# SupplyDigital.net
KiCad netlist of a schematic drawn in Altium Designer
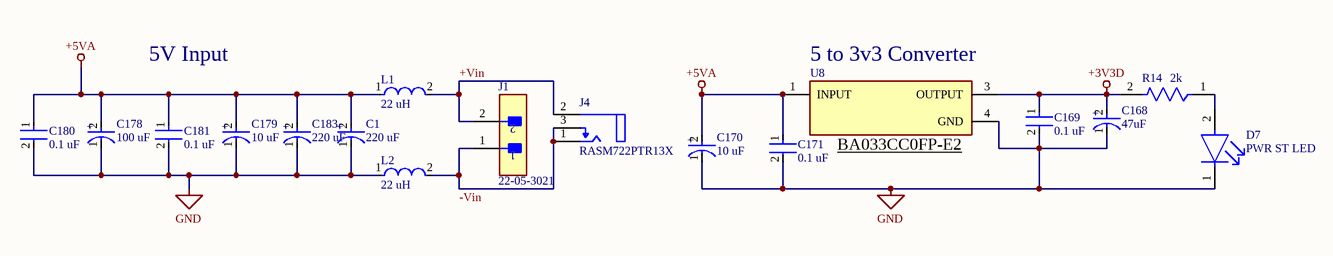
[diagram p0: SupplyDigital.SchDoc]

(export (version "E")
  (design (tool "Eeschema 10.0.6"))
  (components
    (comp (ref "C1")
      (value "220 uF")
      (footprint "FP-SC-MFG")
      (description "CAP ALUM 100UF 20% 10V SMD")
      (fields (field (name "TOLERANCE") "20%"))
      (libsource (lib "Altium Content Vault") (part "a00bbbee19879c290e62620ae7e47b1"))
    )
    (comp (ref "C168")
      (value "47uF")
      (footprint "FP-TAJR-MFG")
      (description "4.7uF 10V  ±10% 9Ω 0805  SMD Tantalum Capacitor")
      (fields (field (name "TOLERANCE") "10%") (field (name "VOLTAGE") "10V"))
      (libsource (lib "Altium Content Vault") (part "203bc49f2ac43e59fd269a8c329ed05"))
    )
    (comp (ref "C169")
      (value "0.1 uF")
      (footprint "FP-CC0805-0_85-MFG")
      (description "CAP CER 0.1UF 25V X7R 0805")
      (fields (field (name "MANUFACTURER PART NUMBER") "CC0805KRX7R8BB104") (field (name "TOLERANCE") "0.1"))
      (libsource (lib "Altium Content Vault") (part "11868f565c42a9108669ba33697ecf6"))
    )
    (comp (ref "C170")
      (value "10 uF")
      (footprint "FP-TAJR-MFG")
      (description "4.7uF 10V  ±10% 9Ω 0805  SMD Tantalum Capacitor")
      (fields (field (name "TOLERANCE") "10%") (field (name "VOLTAGE") "10V"))
      (libsource (lib "Altium Content Vault") (part "203bc49f2ac43e59fd269a8c329ed05"))
    )
    (comp (ref "C171")
      (value "0.1 uF")
      (footprint "FP-CC0805-0_85-MFG")
      (description "CAP CER 0.1UF 25V X7R 0805")
      (fields (field (name "MANUFACTURER PART NUMBER") "CC0805KRX7R8BB104") (field (name "TOLERANCE") "0.1"))
      (libsource (lib "Altium Content Vault") (part "11868f565c42a9108669ba33697ecf6"))
    )
    (comp (ref "C178")
      (value "100 uF")
      (footprint "FP-TAJR-MFG")
      (description "4.7uF 10V  ±10% 9Ω 0805  SMD Tantalum Capacitor")
      (fields (field (name "TOLERANCE") "10%") (field (name "VOLTAGE") "10V"))
      (libsource (lib "Altium Content Vault") (part "203bc49f2ac43e59fd269a8c329ed05"))
    )
    (comp (ref "C179")
      (value "10 uF")
      (footprint "FP-TAJR-MFG")
      (description "4.7uF 10V  ±10% 9Ω 0805  SMD Tantalum Capacitor")
      (fields (field (name "TOLERANCE") "10%") (field (name "VOLTAGE") "10V"))
      (libsource (lib "Altium Content Vault") (part "203bc49f2ac43e59fd269a8c329ed05"))
    )
    (comp (ref "C180")
      (value "0.1 uF")
      (footprint "FP-CC0805-0_85-MFG")
      (description "CAP CER 0.1UF 25V X7R 0805")
      (fields (field (name "MANUFACTURER PART NUMBER") "CC0805KRX7R8BB104") (field (name "TOLERANCE") "0.1"))
      (libsource (lib "Altium Content Vault") (part "11868f565c42a9108669ba33697ecf6"))
    )
    (comp (ref "C181")
      (value "0.1 uF")
      (footprint "FP-CC0805-0_85-MFG")
      (description "CAP CER 0.1UF 25V X7R 0805")
      (fields (field (name "MANUFACTURER PART NUMBER") "CC0805KRX7R8BB104") (field (name "TOLERANCE") "0.1"))
      (libsource (lib "Altium Content Vault") (part "11868f565c42a9108669ba33697ecf6"))
    )
    (comp (ref "C183")
      (value "220 uF")
      (footprint "FP-SC-MFG")
      (description "CAP ALUM 100UF 20% 10V SMD")
      (fields (field (name "TOLERANCE") "20%"))
      (libsource (lib "Altium Content Vault") (part "a00bbbee19879c290e62620ae7e47b1"))
    )
    (comp (ref "D7")
      (value "PWR ST LED")
      (footprint "FP-APHCM2012SYCK-F01-MFG")
      (description "LED YELLOW CLEAR CHIP SMD")
      (libsource (lib "Altium Content Vault") (part "8706943c75ba83719d021d2fdc84c58"))
    )
    (comp (ref "J1")
      (value "22-05-3021")
      (footprint "FP-22-05-3021-MFG")
      (description "CONN HEADER R/A 2POS 2.54MM")
      (libsource (lib "Altium Content Vault") (part "3bc925449376181038e59eaffc5286c"))
    )
    (comp (ref "J4")
      (value "RASM722PTR13X")
      (footprint "FP-RASM722PTR13X-MFG")
      (description "CONN PWR JACK 2.1X5.5MM SOLDER")
      (libsource (lib "Altium Content Vault") (part "69023cd999ddc70d2a190894d9bbb58"))
    )
    (comp (ref "L1")
      (value "22 uH")
      (footprint "FP-LQH44PN_P0-MFG")
      (description "FIXED IND 4.7UH 1.7A 96 MOHM SMD")
      (fields (field (name "TOLERANCE") "20%"))
      (libsource (lib "Altium Content Vault") (part "725321dda6339637d4d059423bc1c3c"))
    )
    (comp (ref "L2")
      (value "22 uH")
      (footprint "FP-LQH44PN_P0-MFG")
      (description "FIXED IND 4.7UH 1.7A 96 MOHM SMD")
      (fields (field (name "TOLERANCE") "20%"))
      (libsource (lib "Altium Content Vault") (part "725321dda6339637d4d059423bc1c3c"))
    )
    (comp (ref "R14")
      (value "2k")
      (footprint "FP-RR1220-MFG")
      (description "49.9Ω ±0.5% 0.1W 1/10W Chip Resistor 0805 (2012 Metric) Thin Film")
      (fields (field (name "TOLERANCE") "0.5%"))
      (libsource (lib "Altium Content Vault") (part "1029c3af85768c4190bb7ad29bc67b5"))
    )
    (comp (ref "U8")
      (value "TLV2217-33KVURG3")
      (footprint "FP-KVU0003A-MFG")
      (description "IC REG LINEAR 3.3V 500MA TO252-3")
      (libsource (lib "Altium Content Vault") (part "d5a15bcdf6b664122197b732e21c3ca"))
    )
  )
  (nets
    (net (code "1") (name "+3V3D") (class "Default")
      (node (ref "C168") (pin "2") (pinfunction "A_2") (pintype "passive"))
      (node (ref "C169") (pin "1") (pinfunction "1_1") (pintype "passive"))
      (node (ref "R14") (pin "2") (pinfunction "2_2") (pintype "passive"))
      (node (ref "U8") (pin "3") (pinfunction "OUTPUT_3") (pintype "passive"))
    )
    (net (code "2") (name "+5VA") (class "Default")
      (node (ref "C1") (pin "2") (pinfunction "A_2") (pintype "passive"))
      (node (ref "C170") (pin "2") (pinfunction "A_2") (pintype "passive"))
      (node (ref "C171") (pin "1") (pinfunction "1_1") (pintype "passive"))
      (node (ref "C178") (pin "2") (pinfunction "A_2") (pintype "passive"))
      (node (ref "C179") (pin "2") (pinfunction "A_2") (pintype "passive"))
      (node (ref "C180") (pin "1") (pinfunction "1_1") (pintype "passive"))
      (node (ref "C181") (pin "1") (pinfunction "1_1") (pintype "passive"))
      (node (ref "C183") (pin "2") (pinfunction "A_2") (pintype "passive"))
      (node (ref "L1") (pin "1") (pinfunction "1_1") (pintype "passive"))
      (node (ref "U8") (pin "1") (pinfunction "INPUT_1") (pintype "passive"))
    )
    (net (code "3") (name "/+Vin") (class "Default")
      (node (ref "J1") (pin "2") (pinfunction "2_2") (pintype "passive"))
      (node (ref "J4") (pin "2") (pinfunction "SLEEVE_TERMINAL_2") (pintype "passive"))
      (node (ref "L1") (pin "2") (pinfunction "2_2") (pintype "passive"))
    )
    (net (code "4") (name "/-Vin") (class "Default")
      (node (ref "J1") (pin "1") (pinfunction "1_1") (pintype "passive"))
      (node (ref "J4") (pin "1") (pinfunction "TIP_TERMINAL(CENTER_PIN)_1") (pintype "passive"))
      (node (ref "J4") (pin "3") (pinfunction "SHUNT_TERMINAL_3") (pintype "passive"))
      (node (ref "L2") (pin "2") (pinfunction "2_2") (pintype "passive"))
    )
    (net (code "5") (name "GND") (class "Default")
      (node (ref "C1") (pin "1") (pinfunction "C_1") (pintype "passive"))
      (node (ref "C168") (pin "1") (pinfunction "C_1") (pintype "passive"))
      (node (ref "C169") (pin "2") (pinfunction "2_2") (pintype "passive"))
      (node (ref "C170") (pin "1") (pinfunction "C_1") (pintype "passive"))
      (node (ref "C171") (pin "2") (pinfunction "2_2") (pintype "passive"))
      (node (ref "C178") (pin "1") (pinfunction "C_1") (pintype "passive"))
      (node (ref "C179") (pin "1") (pinfunction "C_1") (pintype "passive"))
      (node (ref "C180") (pin "2") (pinfunction "2_2") (pintype "passive"))
      (node (ref "C181") (pin "2") (pinfunction "2_2") (pintype "passive"))
      (node (ref "C183") (pin "1") (pinfunction "C_1") (pintype "passive"))
      (node (ref "D7") (pin "1") (pinfunction "C_1") (pintype "passive"))
      (node (ref "L2") (pin "1") (pinfunction "1_1") (pintype "passive"))
      (node (ref "U8") (pin "4") (pinfunction "GND_4") (pintype "power_in"))
    )
    (net (code "6") (name "Net-(D7-A)") (class "Default")
      (node (ref "D7") (pin "2") (pinfunction "A_2") (pintype "passive"))
      (node (ref "R14") (pin "1") (pinfunction "1_1") (pintype "passive"))
    )
  )
)
